# SUP_1V.net
KiCad netlist of a schematic drawn in Altium Designer
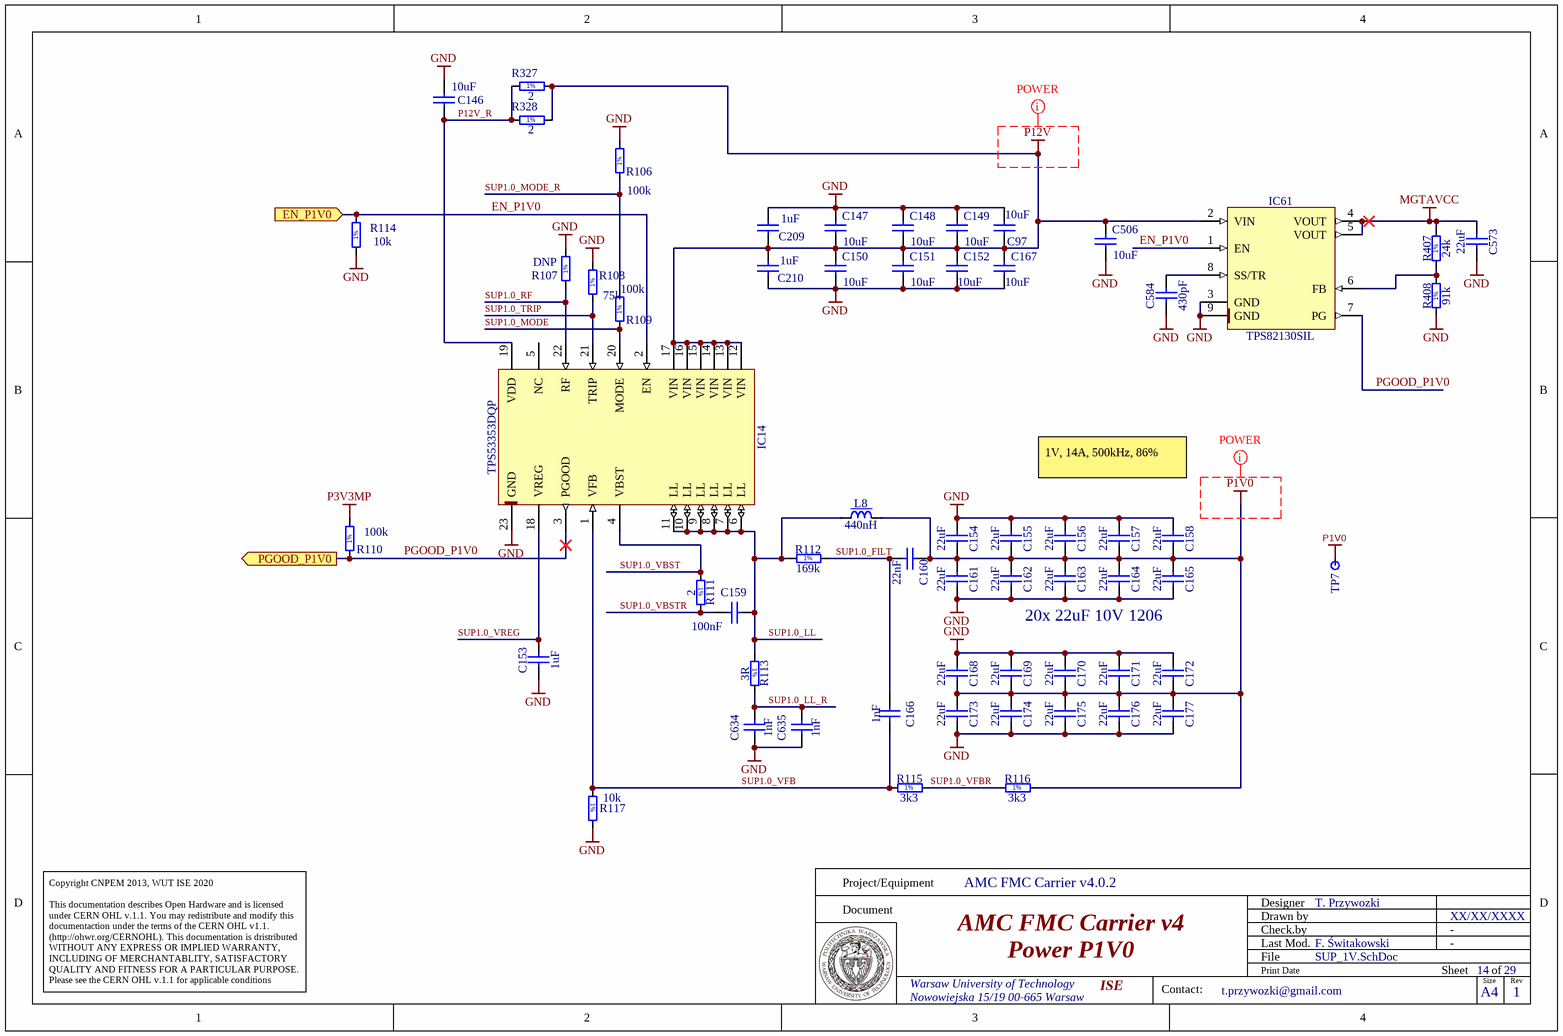
[diagram p0: SUP_1V.SchDoc]

(export (version "E")
  (design (tool "Eeschema 10.0.6"))
  (components
    (comp (ref "C97")
      (value "10uF")
      (footprint "CAPC2012X135N")
      (description "Non-polarised capacitor")
      (fields
        (field (name "PART NUMBER") "CC0805_10UF_16V_10%_X5R")
        (field (name "VOLTAGE") "16V")
        (field (name "AUTHOR") "CERN DEM JLC")
      )
      (libsource (lib "Capacitors") (part "Capacitor - non polarized"))
    )
    (comp (ref "C146")
      (value "10uF")
      (footprint "CAPC2012X135N")
      (description "Non-polarised capacitor")
      (fields
        (field (name "PART NUMBER") "CC0805_10UF_16V_10%_X5R")
        (field (name "VOLTAGE") "16V")
        (field (name "AUTHOR") "CERN DEM JLC")
      )
      (libsource (lib "Capacitors") (part "Capacitor - non polarized"))
    )
    (comp (ref "C147")
      (value "10uF")
      (footprint "CAPC2012X135N")
      (description "Non-polarised capacitor")
      (fields
        (field (name "PART NUMBER") "CC0805_10UF_16V_10%_X5R")
        (field (name "VOLTAGE") "16V")
        (field (name "AUTHOR") "CERN DEM JLC")
      )
      (libsource (lib "Capacitors") (part "Capacitor - non polarized"))
    )
    (comp (ref "C148")
      (value "10uF")
      (footprint "CAPC2012X135N")
      (description "Non-polarised capacitor")
      (fields
        (field (name "PART NUMBER") "CC0805_10UF_16V_10%_X5R")
        (field (name "VOLTAGE") "16V")
        (field (name "AUTHOR") "CERN DEM JLC")
      )
      (libsource (lib "Capacitors") (part "Capacitor - non polarized"))
    )
    (comp (ref "C149")
      (value "10uF")
      (footprint "CAPC2012X135N")
      (description "Non-polarised capacitor")
      (fields
        (field (name "PART NUMBER") "CC0805_10UF_16V_10%_X5R")
        (field (name "VOLTAGE") "16V")
        (field (name "AUTHOR") "CERN DEM JLC")
      )
      (libsource (lib "Capacitors") (part "Capacitor - non polarized"))
    )
    (comp (ref "C150")
      (value "10uF")
      (footprint "CAPC2012X135N")
      (description "Non-polarised capacitor")
      (fields
        (field (name "PART NUMBER") "CC0805_10UF_16V_10%_X5R")
        (field (name "VOLTAGE") "16V")
        (field (name "AUTHOR") "CERN DEM JLC")
      )
      (libsource (lib "Capacitors") (part "Capacitor - non polarized"))
    )
    (comp (ref "C151")
      (value "10uF")
      (footprint "CAPC2012X135N")
      (description "Non-polarised capacitor")
      (fields
        (field (name "PART NUMBER") "CC0805_10UF_16V_10%_X5R")
        (field (name "VOLTAGE") "16V")
        (field (name "AUTHOR") "CERN DEM JLC")
      )
      (libsource (lib "Capacitors") (part "Capacitor - non polarized"))
    )
    (comp (ref "C152")
      (value "10uF")
      (footprint "CAPC2012X135N")
      (description "Non-polarised capacitor")
      (fields
        (field (name "PART NUMBER") "CC0805_10UF_16V_10%_X5R")
        (field (name "VOLTAGE") "16V")
        (field (name "AUTHOR") "CERN DEM JLC")
      )
      (libsource (lib "Capacitors") (part "Capacitor - non polarized"))
    )
    (comp (ref "C153")
      (value "1uF")
      (footprint "CAPC1608X87N")
      (description "Non-polarised capacitor")
      (fields
        (field (name "PART NUMBER") "CC0603_1UF_16V_10%_X7R")
        (field (name "VOLTAGE") "16V")
        (field (name "AUTHOR") "CERN DEM JLC")
      )
      (libsource (lib "Capacitors") (part "Capacitor - non polarized"))
    )
    (comp (ref "C154")
      (value "22uF")
      (footprint "CAPC3216X180N")
      (description "Non-polarised capacitor")
      (fields
        (field (name "PART NUMBER") "CC1206_22UF_10V_10%_X7R")
        (field (name "VOLTAGE") "10V")
        (field (name "AUTHOR") "CERN DEM JLC")
      )
      (libsource (lib "Capacitors") (part "Capacitor - non polarized"))
    )
    (comp (ref "C155")
      (value "22uF")
      (footprint "CAPC3216X180N")
      (description "Non-polarised capacitor")
      (fields
        (field (name "PART NUMBER") "CC1206_22UF_10V_10%_X7R")
        (field (name "VOLTAGE") "10V")
        (field (name "AUTHOR") "CERN DEM JLC")
      )
      (libsource (lib "Capacitors") (part "Capacitor - non polarized"))
    )
    (comp (ref "C156")
      (value "22uF")
      (footprint "CAPC3216X180N")
      (description "Non-polarised capacitor")
      (fields
        (field (name "PART NUMBER") "CC1206_22UF_10V_10%_X7R")
        (field (name "VOLTAGE") "10V")
        (field (name "AUTHOR") "CERN DEM JLC")
      )
      (libsource (lib "Capacitors") (part "Capacitor - non polarized"))
    )
    (comp (ref "C157")
      (value "22uF")
      (footprint "CAPC3216X180N")
      (description "Non-polarised capacitor")
      (fields
        (field (name "PART NUMBER") "CC1206_22UF_10V_10%_X7R")
        (field (name "VOLTAGE") "10V")
        (field (name "AUTHOR") "CERN DEM JLC")
      )
      (libsource (lib "Capacitors") (part "Capacitor - non polarized"))
    )
    (comp (ref "C158")
      (value "22uF")
      (footprint "CAPC3216X180N")
      (description "Non-polarised capacitor")
      (fields
        (field (name "PART NUMBER") "CC1206_22UF_10V_10%_X7R")
        (field (name "VOLTAGE") "10V")
        (field (name "AUTHOR") "CERN DEM JLC")
      )
      (libsource (lib "Capacitors") (part "Capacitor - non polarized"))
    )
    (comp (ref "C159")
      (value "100nF")
      (footprint "CAPC1005X55N")
      (description "Non-polarised capacitor")
      (fields
        (field (name "PART NUMBER") "CC0402_100NF_16V_10%_X7R")
        (field (name "VOLTAGE") "16V")
        (field (name "AUTHOR") "CERN DEM JLC")
      )
      (libsource (lib "Capacitors") (part "Capacitor - non polarized"))
    )
    (comp (ref "C160")
      (value "22nF")
      (footprint "CAPC1608X87N")
      (description "Non-polarised capacitor")
      (fields
        (field (name "PART NUMBER") "CC0603_22NF_50V_10%_X7R")
        (field (name "VOLTAGE") "50V")
        (field (name "AUTHOR") "CERN DEM JLC")
      )
      (libsource (lib "Capacitors") (part "Capacitor - non polarized"))
    )
    (comp (ref "C161")
      (value "22uF")
      (footprint "CAPC3216X180N")
      (description "Non-polarised capacitor")
      (fields
        (field (name "PART NUMBER") "CC1206_22UF_10V_10%_X7R")
        (field (name "VOLTAGE") "10V")
        (field (name "AUTHOR") "CERN DEM JLC")
      )
      (libsource (lib "Capacitors") (part "Capacitor - non polarized"))
    )
    (comp (ref "C162")
      (value "22uF")
      (footprint "CAPC3216X180N")
      (description "Non-polarised capacitor")
      (fields
        (field (name "PART NUMBER") "CC1206_22UF_10V_10%_X7R")
        (field (name "VOLTAGE") "10V")
        (field (name "AUTHOR") "CERN DEM JLC")
      )
      (libsource (lib "Capacitors") (part "Capacitor - non polarized"))
    )
    (comp (ref "C163")
      (value "22uF")
      (footprint "CAPC3216X180N")
      (description "Non-polarised capacitor")
      (fields
        (field (name "PART NUMBER") "CC1206_22UF_10V_10%_X7R")
        (field (name "VOLTAGE") "10V")
        (field (name "AUTHOR") "CERN DEM JLC")
      )
      (libsource (lib "Capacitors") (part "Capacitor - non polarized"))
    )
    (comp (ref "C164")
      (value "22uF")
      (footprint "CAPC3216X180N")
      (description "Non-polarised capacitor")
      (fields
        (field (name "PART NUMBER") "CC1206_22UF_10V_10%_X7R")
        (field (name "VOLTAGE") "10V")
        (field (name "AUTHOR") "CERN DEM JLC")
      )
      (libsource (lib "Capacitors") (part "Capacitor - non polarized"))
    )
    (comp (ref "C165")
      (value "22uF")
      (footprint "CAPC3216X180N")
      (description "Non-polarised capacitor")
      (fields
        (field (name "PART NUMBER") "CC1206_22UF_10V_10%_X7R")
        (field (name "VOLTAGE") "10V")
        (field (name "AUTHOR") "CERN DEM JLC")
      )
      (libsource (lib "Capacitors") (part "Capacitor - non polarized"))
    )
    (comp (ref "C166")
      (value "1nF")
      (footprint "CAPC1005X55N")
      (description "Non-polarised capacitor")
      (fields
        (field (name "PART NUMBER") "CC0402_1NF_50V_10%_X7R")
        (field (name "VOLTAGE") "50V")
        (field (name "AUTHOR") "CERN DEM JLC")
      )
      (libsource (lib "Capacitors") (part "Capacitor - non polarized"))
    )
    (comp (ref "C167")
      (value "10uF")
      (footprint "CAPC2012X135N")
      (description "Non-polarised capacitor")
      (fields
        (field (name "PART NUMBER") "CC0805_10UF_16V_10%_X5R")
        (field (name "VOLTAGE") "16V")
        (field (name "AUTHOR") "CERN DEM JLC")
      )
      (libsource (lib "Capacitors") (part "Capacitor - non polarized"))
    )
    (comp (ref "C168")
      (value "22uF")
      (footprint "CAPC3216X180N")
      (description "Non-polarised capacitor")
      (fields
        (field (name "PART NUMBER") "CC1206_22UF_10V_10%_X7R")
        (field (name "VOLTAGE") "10V")
        (field (name "AUTHOR") "CERN DEM JLC")
      )
      (libsource (lib "Capacitors") (part "Capacitor - non polarized"))
    )
    (comp (ref "C169")
      (value "22uF")
      (footprint "CAPC3216X180N")
      (description "Non-polarised capacitor")
      (fields
        (field (name "PART NUMBER") "CC1206_22UF_10V_10%_X7R")
        (field (name "VOLTAGE") "10V")
        (field (name "AUTHOR") "CERN DEM JLC")
      )
      (libsource (lib "Capacitors") (part "Capacitor - non polarized"))
    )
    (comp (ref "C170")
      (value "22uF")
      (footprint "CAPC3216X180N")
      (description "Non-polarised capacitor")
      (fields
        (field (name "PART NUMBER") "CC1206_22UF_10V_10%_X7R")
        (field (name "VOLTAGE") "10V")
        (field (name "AUTHOR") "CERN DEM JLC")
      )
      (libsource (lib "Capacitors") (part "Capacitor - non polarized"))
    )
    (comp (ref "C171")
      (value "22uF")
      (footprint "CAPC3216X180N")
      (description "Non-polarised capacitor")
      (fields
        (field (name "PART NUMBER") "CC1206_22UF_10V_10%_X7R")
        (field (name "VOLTAGE") "10V")
        (field (name "AUTHOR") "CERN DEM JLC")
      )
      (libsource (lib "Capacitors") (part "Capacitor - non polarized"))
    )
    (comp (ref "C172")
      (value "22uF")
      (footprint "CAPC3216X180N")
      (description "Non-polarised capacitor")
      (fields
        (field (name "PART NUMBER") "CC1206_22UF_10V_10%_X7R")
        (field (name "VOLTAGE") "10V")
        (field (name "AUTHOR") "CERN DEM JLC")
      )
      (libsource (lib "Capacitors") (part "Capacitor - non polarized"))
    )
    (comp (ref "C173")
      (value "22uF")
      (footprint "CAPC3216X180N")
      (description "Non-polarised capacitor")
      (fields
        (field (name "PART NUMBER") "CC1206_22UF_10V_10%_X7R")
        (field (name "VOLTAGE") "10V")
        (field (name "AUTHOR") "CERN DEM JLC")
      )
      (libsource (lib "Capacitors") (part "Capacitor - non polarized"))
    )
    (comp (ref "C174")
      (value "22uF")
      (footprint "CAPC3216X180N")
      (description "Non-polarised capacitor")
      (fields
        (field (name "PART NUMBER") "CC1206_22UF_10V_10%_X7R")
        (field (name "VOLTAGE") "10V")
        (field (name "AUTHOR") "CERN DEM JLC")
      )
      (libsource (lib "Capacitors") (part "Capacitor - non polarized"))
    )
    (comp (ref "C175")
      (value "22uF")
      (footprint "CAPC3216X180N")
      (description "Non-polarised capacitor")
      (fields
        (field (name "PART NUMBER") "CC1206_22UF_10V_10%_X7R")
        (field (name "VOLTAGE") "10V")
        (field (name "AUTHOR") "CERN DEM JLC")
      )
      (libsource (lib "Capacitors") (part "Capacitor - non polarized"))
    )
    (comp (ref "C176")
      (value "22uF")
      (footprint "CAPC3216X180N")
      (description "Non-polarised capacitor")
      (fields
        (field (name "PART NUMBER") "CC1206_22UF_10V_10%_X7R")
        (field (name "VOLTAGE") "10V")
        (field (name "AUTHOR") "CERN DEM JLC")
      )
      (libsource (lib "Capacitors") (part "Capacitor - non polarized"))
    )
    (comp (ref "C177")
      (value "22uF")
      (footprint "CAPC3216X180N")
      (description "Non-polarised capacitor")
      (fields
        (field (name "PART NUMBER") "CC1206_22UF_10V_10%_X7R")
        (field (name "VOLTAGE") "10V")
        (field (name "AUTHOR") "CERN DEM JLC")
      )
      (libsource (lib "Capacitors") (part "Capacitor - non polarized"))
    )
    (comp (ref "C209")
      (value "1uF")
      (footprint "CAPC1608X87N")
      (description "Non-polarised capacitor")
      (fields
        (field (name "PART NUMBER") "CC0603_1UF_16V_10%_X7R")
        (field (name "VOLTAGE") "16V")
        (field (name "AUTHOR") "CERN DEM JLC")
      )
      (libsource (lib "Capacitors") (part "Capacitor - non polarized"))
    )
    (comp (ref "C210")
      (value "1uF")
      (footprint "CAPC1608X87N")
      (description "Non-polarised capacitor")
      (fields
        (field (name "PART NUMBER") "CC0603_1UF_16V_10%_X7R")
        (field (name "VOLTAGE") "16V")
        (field (name "AUTHOR") "CERN DEM JLC")
      )
      (libsource (lib "Capacitors") (part "Capacitor - non polarized"))
    )
    (comp (ref "C506")
      (value "10uF")
      (footprint "CAPC2012X135N")
      (description "Non-polarised capacitor")
      (fields
        (field (name "PART NUMBER") "CC0805_10UF_16V_10%_X5R")
        (field (name "VOLTAGE") "16V")
        (field (name "AUTHOR") "CERN DEM JLC")
      )
      (libsource (lib "Capacitors") (part "Capacitor - non polarized"))
    )
    (comp (ref "C573")
      (value "22uF")
      (footprint "CAPC3216X180N")
      (description "Non-polarised capacitor")
      (fields
        (field (name "PART NUMBER") "CC1206_22UF_10V_10%_X7R")
        (field (name "VOLTAGE") "10V")
        (field (name "AUTHOR") "CERN DEM JLC")
      )
      (libsource (lib "Capacitors") (part "Capacitor - non polarized"))
    )
    (comp (ref "C584")
      (value "430pF")
      (footprint "CAPC1608X100N")
      (description "Non-polarised capacitor")
      (fields
        (field (name "PART NUMBER") "CC0603_430PF_25V_10%_C0G_VISHAY_VJ0603D431KLX")
        (field (name "VOLTAGE") "25V")
        (field (name "AUTHOR") "CERN DEM BC")
      )
      (libsource (lib "Capacitors") (part "Capacitor - non polarized"))
    )
    (comp (ref "C634")
      (value "1nF")
      (footprint "CAPC1005X55N")
      (description "Non-polarised capacitor")
      (fields
        (field (name "PART NUMBER") "CC0402_1NF_50V_10%_X7R")
        (field (name "VOLTAGE") "50V")
        (field (name "AUTHOR") "CERN DEM JLC")
      )
      (libsource (lib "Capacitors") (part "Capacitor - non polarized"))
    )
    (comp (ref "C635")
      (value "1nF")
      (footprint "CAPC1005X55N")
      (description "Non-polarised capacitor")
      (fields
        (field (name "PART NUMBER") "CC0402_1NF_50V_10%_X7R")
        (field (name "VOLTAGE") "50V")
        (field (name "AUTHOR") "CERN DEM JLC")
      )
      (libsource (lib "Capacitors") (part "Capacitor - non polarized"))
    )
    (comp (ref "IC14")
      (value "TPS53353DQP")
      (footprint "SON50P500X600X150-23N-R334X557")
      (description "1.5V to 15V Input (4.5V to 25V Bias), 20A Synchronous Buck SWIFT™ Converter with Eco-mode™")
      (fields (field (name "MANUFACTURER") "TEXAS INSTRUMENTS") (field (name "AUTHOR") "CERN DEM BC"))
      (libsource (lib "ICs And Semiconductors") (part "TPS53353"))
    )
    (comp (ref "IC61")
      (value "TPS82130SIL")
      (footprint "TEXAS_SIL0008D (uSIP)")
      (description "3V to 17V Input 3A Step-Down Converter MicroSiP™ Module with Integrated Inductor")
      (fields (field (name "MANUFACTURER") "TEXAS INSTRUMENTS") (field (name "AUTHOR") "CERN DEM BC"))
      (libsource (lib "ICs And Semiconductors") (part "TPS82130"))
    )
    (comp (ref "L8")
      (value "440nH")
      (footprint "IND_PULSE_PA0513")
      (description "Inductor With Core")
      (fields
        (field (name "PART NUMBER") "IND_440NH_20%_PULSE_PA0513.441NLT")
        (field (name "POWER") "30A")
        (field (name "AUTHOR") "CERN DEM JLC")
      )
      (libsource (lib "Inductors & Transformers") (part "Inductor With Magnetic core"))
    )
    (comp (ref "R106")
      (value "100k")
      (footprint "RESC1005X40N")
      (description "Resistor - 1%")
      (fields
        (field (name "PART NUMBER") "R0402_100K_1%_0.0625W_100PPM")
        (field (name "POWER") "0.0625W")
        (field (name "AUTHOR") "CERN DEM JLC")
      )
      (libsource (lib "Resistors") (part "Resistor - 1%"))
    )
    (comp (ref "R107")
      (value "DNP")
      (footprint "RESC1608X55N")
      (description "Resistor - 1%")
      (fields
        (field (name "PART NUMBER") "R0603_75K_1%_0.1W_100PPM")
        (field (name "POWER") "0.1W")
        (field (name "AUTHOR") "CERN DEM JLC")
      )
      (libsource (lib "Resistors") (part "Resistor - 1%"))
    )
    (comp (ref "R108")
      (value "75k")
      (footprint "RESC1608X55N")
      (description "Resistor - 1%")
      (fields
        (field (name "PART NUMBER") "R0603_75K_1%_0.1W_100PPM")
        (field (name "POWER") "0.1W")
        (field (name "AUTHOR") "CERN DEM JLC")
      )
      (libsource (lib "Resistors") (part "Resistor - 1%"))
    )
    (comp (ref "R109")
      (value "100k")
      (footprint "RESC1005X40N")
      (description "Resistor - 1%")
      (fields
        (field (name "PART NUMBER") "R0402_100K_1%_0.0625W_100PPM")
        (field (name "POWER") "0.0625W")
        (field (name "AUTHOR") "CERN DEM JLC")
      )
      (libsource (lib "Resistors") (part "Resistor - 1%"))
    )
    (comp (ref "R110")
      (value "100k")
      (footprint "RESC1005X40N")
      (description "Resistor - 1%")
      (fields
        (field (name "PART NUMBER") "R0402_100K_1%_0.0625W_100PPM")
        (field (name "POWER") "0.0625W")
        (field (name "AUTHOR") "CERN DEM JLC")
      )
      (libsource (lib "Resistors") (part "Resistor - 1%"))
    )
    (comp (ref "R111")
      (value "2")
      (footprint "RESC1608X55N")
      (description "Resistor - 1%")
      (fields
        (field (name "PART NUMBER") "R0603_2R_1%_0.1W_200PPM")
        (field (name "POWER") "0.1W")
        (field (name "AUTHOR") "CERN DEM JLC")
      )
      (libsource (lib "Resistors") (part "Resistor - 1%"))
    )
    (comp (ref "R112")
      (value "169k")
      (footprint "RESC1608X55N")
      (description "Resistor - 1%")
      (fields
        (field (name "PART NUMBER") "R0603_169k_1%_0.1W_100PPM")
        (field (name "POWER") "0.1W")
        (field (name "AUTHOR") "CERN DEM JLC")
      )
      (libsource (lib "Resistors") (part "Resistor - 1%"))
    )
    (comp (ref "R113")
      (value "3R")
      (footprint "RESC3216X65N")
      (description "Resistor - 1%")
      (fields
        (field (name "PART NUMBER") "R1206_3R_1%_0.25W_200PPM")
        (field (name "POWER") "0.25W")
        (field (name "AUTHOR") "CERN DEM JLC")
      )
      (libsource (lib "Resistors") (part "Resistor - 1%"))
    )
    (comp (ref "R114")
      (value "10k")
      (footprint "RESC1005X40N")
      (description "Resistor - 1%")
      (fields
        (field (name "PART NUMBER") "R0402_10K_1%_0.0625W_100PPM")
        (field (name "POWER") "0.0625W")
        (field (name "AUTHOR") "CERN DEM JLC")
      )
      (libsource (lib "Resistors") (part "Resistor - 1%"))
    )
    (comp (ref "R115")
      (value "3k3")
      (footprint "RESC1608X55N")
      (description "Resistor - 1%")
      (fields
        (field (name "PART NUMBER") "R0603_3K3_1%_0.1W_100PPM")
        (field (name "POWER") "0.1W")
        (field (name "AUTHOR") "CERN DEM JLC")
      )
      (libsource (lib "Resistors") (part "Resistor - 1%"))
    )
    (comp (ref "R116")
      (value "3k3")
      (footprint "RESC1608X55N")
      (description "Resistor - 1%")
      (fields
        (field (name "PART NUMBER") "R0603_3K3_1%_0.1W_100PPM")
        (field (name "POWER") "0.1W")
        (field (name "AUTHOR") "CERN DEM JLC")
      )
      (libsource (lib "Resistors") (part "Resistor - 1%"))
    )
    (comp (ref "R117")
      (value "10k")
      (footprint "RESC1005X40N")
      (description "Resistor - 1%")
      (fields
        (field (name "PART NUMBER") "R0402_10K_1%_0.0625W_100PPM")
        (field (name "POWER") "0.0625W")
        (field (name "AUTHOR") "CERN DEM JLC")
      )
      (libsource (lib "Resistors") (part "Resistor - 1%"))
    )
    (comp (ref "R327")
      (value "2")
      (footprint "RESC1608X55N")
      (description "Resistor - 1%")
      (fields
        (field (name "PART NUMBER") "R0603_2R_1%_0.1W_200PPM")
        (field (name "POWER") "0.1W")
        (field (name "AUTHOR") "CERN DEM JLC")
      )
      (libsource (lib "Resistors") (part "Resistor - 1%"))
    )
    (comp (ref "R328")
      (value "2")
      (footprint "RESC1608X55N")
      (description "Resistor - 1%")
      (fields
        (field (name "PART NUMBER") "R0603_2R_1%_0.1W_200PPM")
        (field (name "POWER") "0.1W")
        (field (name "AUTHOR") "CERN DEM JLC")
      )
      (libsource (lib "Resistors") (part "Resistor - 1%"))
    )
    (comp (ref "R407")
      (value "24k")
      (footprint "RESC1005X40N")
      (description "Resistor - 1%")
      (fields
        (field (name "PART NUMBER") "R0402_24K_1%_0.0625W_100PPM")
        (field (name "POWER") "0.0625W")
        (field (name "AUTHOR") "CERN DEM JLC")
      )
      (libsource (lib "Resistors") (part "Resistor - 1%"))
    )
    (comp (ref "R408")
      (value "91k")
      (footprint "RESC1005X40N")
      (description "Resistor - 1%")
      (fields
        (field (name "PART NUMBER") "R0402_91K_1%_0.0625W_100PPM")
        (field (name "POWER") "0.0625W")
        (field (name "AUTHOR") "CERN DEM JLC")
      )
      (libsource (lib "Resistors") (part "Resistor - 1%"))
    )
    (comp (ref "TP7")
      (value "Test Point")
      (footprint "TPS127")
      (fields (field (name "PART NUMBER") "SMD_PAD_1.27X1.27MM") (field (name "AUTHOR") "CERN DEM JLC"))
      (libsource (lib "Eletro-mechanical") (part "Test Point"))
    )
  )
  (nets
    (net (code "1") (name "/EN_P1V0") (class "Default")
      (node (ref "IC14") (pin "2") (pinfunction "EN_2") (pintype "input"))
      (node (ref "IC61") (pin "1") (pinfunction "EN_1") (pintype "input"))
      (node (ref "R114") (pin "2") (pinfunction "2_2") (pintype "passive"))
    )
    (net (code "2") (name "/P12V_R") (class "Default")
      (node (ref "C146") (pin "1") (pinfunction "1_1") (pintype "passive"))
      (node (ref "IC14") (pin "19") (pinfunction "VDD_19") (pintype "power_in"))
      (node (ref "R327") (pin "1") (pinfunction "1_1") (pintype "passive"))
      (node (ref "R328") (pin "1") (pinfunction "1_1") (pintype "passive"))
    )
    (net (code "3") (name "/PGOOD_P1V0") (class "Default")
      (node (ref "IC14") (pin "3") (pinfunction "PGOOD_3") (pintype "output"))
      (node (ref "IC61") (pin "7") (pinfunction "PG_7") (pintype "output"))
      (node (ref "R110") (pin "1") (pinfunction "1_1") (pintype "passive"))
    )
    (net (code "4") (name "/SUP1.0_FILT") (class "Default")
      (node (ref "C160") (pin "1") (pinfunction "1_1") (pintype "passive"))
      (node (ref "C166") (pin "2") (pinfunction "2_2") (pintype "passive"))
      (node (ref "R112") (pin "2") (pinfunction "2_2") (pintype "passive"))
    )
    (net (code "5") (name "/SUP1.0_LL") (class "Default")
      (node (ref "C159") (pin "1") (pinfunction "1_1") (pintype "passive"))
      (node (ref "IC14") (pin "10") (pinfunction "LL_10") (pintype "bidirectional"))
      (node (ref "IC14") (pin "11") (pinfunction "LL_11") (pintype "bidirectional"))
      (node (ref "IC14") (pin "6") (pinfunction "LL_6") (pintype "bidirectional"))
      (node (ref "IC14") (pin "7") (pinfunction "LL_7") (pintype "bidirectional"))
      (node (ref "IC14") (pin "8") (pinfunction "LL_8") (pintype "bidirectional"))
      (node (ref "IC14") (pin "9") (pinfunction "LL_9") (pintype "bidirectional"))
      (node (ref "L8") (pin "1") (pinfunction "1_1") (pintype "passive"))
      (node (ref "R112") (pin "1") (pinfunction "1_1") (pintype "passive"))
      (node (ref "R113") (pin "1") (pinfunction "1_1") (pintype "passive"))
    )
    (net (code "6") (name "/SUP1.0_LL_R") (class "Default")
      (node (ref "C634") (pin "1") (pinfunction "1_1") (pintype "passive"))
      (node (ref "C635") (pin "1") (pinfunction "1_1") (pintype "passive"))
      (node (ref "R113") (pin "2") (pinfunction "2_2") (pintype "passive"))
    )
    (net (code "7") (name "/SUP1.0_MODE") (class "Default")
      (node (ref "IC14") (pin "20") (pinfunction "MODE_20") (pintype "input"))
      (node (ref "R109") (pin "1") (pinfunction "1_1") (pintype "passive"))
    )
    (net (code "8") (name "/SUP1.0_MODE_R") (class "Default")
      (node (ref "R106") (pin "1") (pinfunction "1_1") (pintype "passive"))
      (node (ref "R109") (pin "2") (pinfunction "2_2") (pintype "passive"))
    )
    (net (code "9") (name "/SUP1.0_RF") (class "Default")
      (node (ref "IC14") (pin "22") (pinfunction "RF_22") (pintype "input"))
      (node (ref "R107") (pin "1") (pinfunction "1_1") (pintype "passive"))
    )
    (net (code "10") (name "/SUP1.0_TRIP") (class "Default")
      (node (ref "IC14") (pin "21") (pinfunction "TRIP_21") (pintype "input"))
      (node (ref "R108") (pin "1") (pinfunction "1_1") (pintype "passive"))
    )
    (net (code "11") (name "/SUP1.0_VBST") (class "Default")
      (node (ref "IC14") (pin "4") (pinfunction "VBST_4") (pintype "power_in"))
      (node (ref "R111") (pin "1") (pinfunction "1_1") (pintype "passive"))
    )
    (net (code "12") (name "/SUP1.0_VBSTR") (class "Default")
      (node (ref "C159") (pin "2") (pinfunction "2_2") (pintype "passive"))
      (node (ref "R111") (pin "2") (pinfunction "2_2") (pintype "passive"))
    )
    (net (code "13") (name "/SUP1.0_VFB") (class "Default")
      (node (ref "C166") (pin "1") (pinfunction "1_1") (pintype "passive"))
      (node (ref "IC14") (pin "1") (pinfunction "VFB_1") (pintype "input"))
      (node (ref "R115") (pin "1") (pinfunction "1_1") (pintype "passive"))
      (node (ref "R117") (pin "1") (pinfunction "1_1") (pintype "passive"))
    )
    (net (code "14") (name "/SUP1.0_VFBR") (class "Default")
      (node (ref "R115") (pin "2") (pinfunction "2_2") (pintype "passive"))
      (node (ref "R116") (pin "1") (pinfunction "1_1") (pintype "passive"))
    )
    (net (code "15") (name "/SUP1.0_VREG") (class "Default")
      (node (ref "C153") (pin "2") (pinfunction "2_2") (pintype "passive"))
      (node (ref "IC14") (pin "18") (pinfunction "VREG_18") (pintype "power_in"))
    )
    (net (code "16") (name "GND") (class "Default")
      (node (ref "C146") (pin "2") (pinfunction "2_2") (pintype "passive"))
      (node (ref "C147") (pin "2") (pinfunction "2_2") (pintype "passive"))
      (node (ref "C148") (pin "2") (pinfunction "2_2") (pintype "passive"))
      (node (ref "C149") (pin "2") (pinfunction "2_2") (pintype "passive"))
      (node (ref "C150") (pin "1") (pinfunction "1_1") (pintype "passive"))
      (node (ref "C151") (pin "1") (pinfunction "1_1") (pintype "passive"))
      (node (ref "C152") (pin "1") (pinfunction "1_1") (pintype "passive"))
      (node (ref "C153") (pin "1") (pinfunction "1_1") (pintype "passive"))
      (node (ref "C154") (pin "1") (pinfunction "1_1") (pintype "passive"))
      (node (ref "C155") (pin "1") (pinfunction "1_1") (pintype "passive"))
      (node (ref "C156") (pin "1") (pinfunction "1_1") (pintype "passive"))
      (node (ref "C157") (pin "1") (pinfunction "1_1") (pintype "passive"))
      (node (ref "C158") (pin "1") (pinfunction "1_1") (pintype "passive"))
      (node (ref "C161") (pin "2") (pinfunction "2_2") (pintype "passive"))
      (node (ref "C162") (pin "2") (pinfunction "2_2") (pintype "passive"))
      (node (ref "C163") (pin "2") (pinfunction "2_2") (pintype "passive"))
      (node (ref "C164") (pin "2") (pinfunction "2_2") (pintype "passive"))
      (node (ref "C165") (pin "2") (pinfunction "2_2") (pintype "passive"))
      (node (ref "C167") (pin "1") (pinfunction "1_1") (pintype "passive"))
      (node (ref "C168") (pin "1") (pinfunction "1_1") (pintype "passive"))
      (node (ref "C169") (pin "1") (pinfunction "1_1") (pintype "passive"))
      (node (ref "C170") (pin "1") (pinfunction "1_1") (pintype "passive"))
      (node (ref "C171") (pin "1") (pinfunction "1_1") (pintype "passive"))
      (node (ref "C172") (pin "1") (pinfunction "1_1") (pintype "passive"))
      (node (ref "C173") (pin "2") (pinfunction "2_2") (pintype "passive"))
      (node (ref "C174") (pin "2") (pinfunction "2_2") (pintype "passive"))
      (node (ref "C175") (pin "2") (pinfunction "2_2") (pintype "passive"))
      (node (ref "C176") (pin "2") (pinfunction "2_2") (pintype "passive"))
      (node (ref "C177") (pin "2") (pinfunction "2_2") (pintype "passive"))
      (node (ref "C209") (pin "2") (pinfunction "2_2") (pintype "passive"))
      (node (ref "C210") (pin "1") (pinfunction "1_1") (pintype "passive"))
      (node (ref "C506") (pin "1") (pinfunction "1_1") (pintype "passive"))
      (node (ref "C573") (pin "2") (pinfunction "2_2") (pintype "passive"))
      (node (ref "C584") (pin "1") (pinfunction "1_1") (pintype "passive"))
      (node (ref "C634") (pin "2") (pinfunction "2_2") (pintype "passive"))
      (node (ref "C635") (pin "2") (pinfunction "2_2") (pintype "passive"))
      (node (ref "C97") (pin "1") (pinfunction "1_1") (pintype "passive"))
      (node (ref "IC14") (pin "23") (pinfunction "GND_23") (pintype "power_in"))
      (node (ref "IC61") (pin "3") (pinfunction "GND_3") (pintype "power_in"))
      (node (ref "IC61") (pin "9") (pinfunction "GND_9") (pintype "power_in"))
      (node (ref "R106") (pin "2") (pinfunction "2_2") (pintype "passive"))
      (node (ref "R107") (pin "2") (pinfunction "2_2") (pintype "passive"))
      (node (ref "R108") (pin "2") (pinfunction "2_2") (pintype "passive"))
      (node (ref "R114") (pin "1") (pinfunction "1_1") (pintype "passive"))
      (node (ref "R117") (pin "2") (pinfunction "2_2") (pintype "passive"))
      (node (ref "R408") (pin "1") (pinfunction "1_1") (pintype "passive"))
    )
    (net (code "17") (name "MGTAVCC") (class "Default")
      (node (ref "C573") (pin "1") (pinfunction "1_1") (pintype "passive"))
      (node (ref "IC61") (pin "4") (pinfunction "VOUT_4") (pintype "output"))
      (node (ref "IC61") (pin "5") (pinfunction "VOUT_5") (pintype "output"))
      (node (ref "R407") (pin "2") (pinfunction "2_2") (pintype "passive"))
    )
    (net (code "18") (name "Net-(IC61-FB)") (class "Default")
      (node (ref "IC61") (pin "6") (pinfunction "FB_6") (pintype "input"))
      (node (ref "R407") (pin "1") (pinfunction "1_1") (pintype "passive"))
      (node (ref "R408") (pin "2") (pinfunction "2_2") (pintype "passive"))
    )
    (net (code "19") (name "Net-(IC61-SS{slash}TR)") (class "Default")
      (node (ref "C584") (pin "2") (pinfunction "2_2") (pintype "passive"))
      (node (ref "IC61") (pin "8") (pinfunction "SS/TR_8") (pintype "input"))
    )
    (net (code "20") (name "P1V0") (class "Default")
      (node (ref "C154") (pin "2") (pinfunction "2_2") (pintype "passive"))
      (node (ref "C155") (pin "2") (pinfunction "2_2") (pintype "passive"))
      (node (ref "C156") (pin "2") (pinfunction "2_2") (pintype "passive"))
      (node (ref "C157") (pin "2") (pinfunction "2_2") (pintype "passive"))
      (node (ref "C158") (pin "2") (pinfunction "2_2") (pintype "passive"))
      (node (ref "C160") (pin "2") (pinfunction "2_2") (pintype "passive"))
      (node (ref "C161") (pin "1") (pinfunction "1_1") (pintype "passive"))
      (node (ref "C162") (pin "1") (pinfunction "1_1") (pintype "passive"))
      (node (ref "C163") (pin "1") (pinfunction "1_1") (pintype "passive"))
      (node (ref "C164") (pin "1") (pinfunction "1_1") (pintype "passive"))
      (node (ref "C165") (pin "1") (pinfunction "1_1") (pintype "passive"))
      (node (ref "C168") (pin "2") (pinfunction "2_2") (pintype "passive"))
      (node (ref "C169") (pin "2") (pinfunction "2_2") (pintype "passive"))
      (node (ref "C170") (pin "2") (pinfunction "2_2") (pintype "passive"))
      (node (ref "C171") (pin "2") (pinfunction "2_2") (pintype "passive"))
      (node (ref "C172") (pin "2") (pinfunction "2_2") (pintype "passive"))
      (node (ref "C173") (pin "1") (pinfunction "1_1") (pintype "passive"))
      (node (ref "C174") (pin "1") (pinfunction "1_1") (pintype "passive"))
      (node (ref "C175") (pin "1") (pinfunction "1_1") (pintype "passive"))
      (node (ref "C176") (pin "1") (pinfunction "1_1") (pintype "passive"))
      (node (ref "C177") (pin "1") (pinfunction "1_1") (pintype "passive"))
      (node (ref "L8") (pin "2") (pinfunction "2_2") (pintype "passive"))
      (node (ref "R116") (pin "2") (pinfunction "2_2") (pintype "passive"))
      (node (ref "TP7") (pin "1") (pinfunction "1_1") (pintype "bidirectional"))
    )
    (net (code "21") (name "P3V3MP") (class "Default")
      (node (ref "R110") (pin "2") (pinfunction "2_2") (pintype "passive"))
    )
    (net (code "22") (name "P12V") (class "Default")
      (node (ref "C147") (pin "1") (pinfunction "1_1") (pintype "passive"))
      (node (ref "C148") (pin "1") (pinfunction "1_1") (pintype "passive"))
      (node (ref "C149") (pin "1") (pinfunction "1_1") (pintype "passive"))
      (node (ref "C150") (pin "2") (pinfunction "2_2") (pintype "passive"))
      (node (ref "C151") (pin "2") (pinfunction "2_2") (pintype "passive"))
      (node (ref "C152") (pin "2") (pinfunction "2_2") (pintype "passive"))
      (node (ref "C167") (pin "2") (pinfunction "2_2") (pintype "passive"))
      (node (ref "C209") (pin "1") (pinfunction "1_1") (pintype "passive"))
      (node (ref "C210") (pin "2") (pinfunction "2_2") (pintype "passive"))
      (node (ref "C506") (pin "2") (pinfunction "2_2") (pintype "passive"))
      (node (ref "C97") (pin "2") (pinfunction "2_2") (pintype "passive"))
      (node (ref "IC14") (pin "12") (pinfunction "VIN_12") (pintype "power_in"))
      (node (ref "IC14") (pin "13") (pinfunction "VIN_13") (pintype "power_in"))
      (node (ref "IC14") (pin "14") (pinfunction "VIN_14") (pintype "power_in"))
      (node (ref "IC14") (pin "15") (pinfunction "VIN_15") (pintype "power_in"))
      (node (ref "IC14") (pin "16") (pinfunction "VIN_16") (pintype "power_in"))
      (node (ref "IC14") (pin "17") (pinfunction "VIN_17") (pintype "power_in"))
      (node (ref "IC61") (pin "2") (pinfunction "VIN_2") (pintype "input"))
      (node (ref "R327") (pin "2") (pinfunction "2_2") (pintype "passive"))
      (node (ref "R328") (pin "2") (pinfunction "2_2") (pintype "passive"))
    )
    (net (code "23") (name "unconnected-(IC14-NC-Pad5)") (class "Default")
      (node (ref "IC14") (pin "5") (pinfunction "NC_5") (pintype "passive"))
    )
  )
)
